# PillEndo-MkI_CAM4.net
KiCad netlist of a schematic drawn in EAGLE
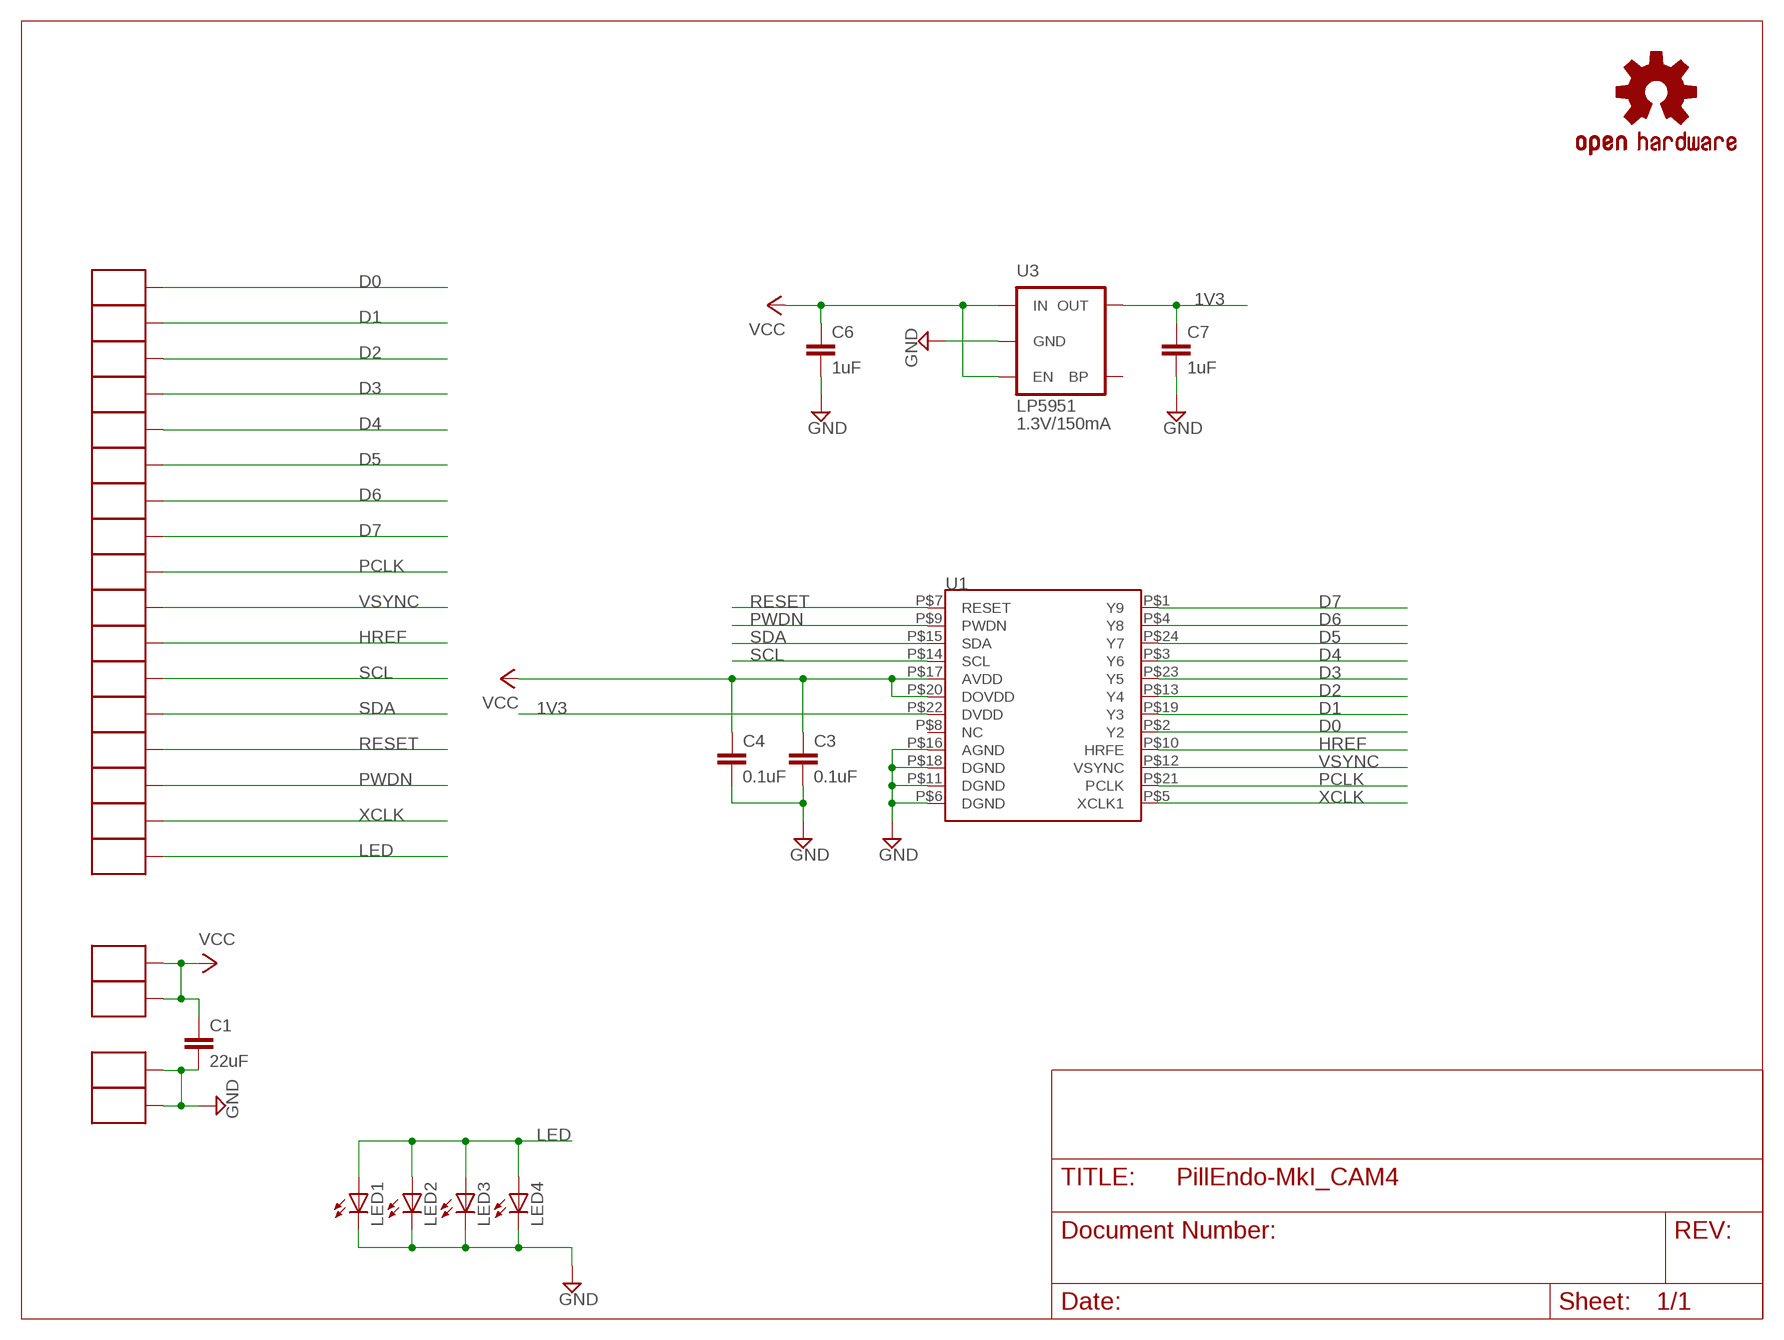
[diagram p0: schematic, sheet 1]

(export (version "E")
  (design (tool "Eeschema 10.0.6"))
  (components
    (comp (ref "C1")
      (value "22uF")
      (footprint "eagle-import:C0603")
      (libsource (lib "eagle-import") (part "C0603"))
    )
    (comp (ref "C3")
      (value "0.1uF")
      (footprint "eagle-import:C0201")
      (libsource (lib "eagle-import") (part "C-EUC0201"))
    )
    (comp (ref "C4")
      (value "0.1uF")
      (footprint "eagle-import:C0201")
      (libsource (lib "eagle-import") (part "C-EUC0201"))
    )
    (comp (ref "C6")
      (value "1uF")
      (footprint "eagle-import:C0402")
      (libsource (lib "eagle-import") (part "C-EUC0402"))
    )
    (comp (ref "C7")
      (value "1uF")
      (footprint "eagle-import:C0402")
      (libsource (lib "eagle-import") (part "C-EUC0402"))
    )
    (comp (ref "LED1")
      (value "LED")
      (footprint "eagle-import:SMARTLED-TTW")
      (libsource (lib "eagle-import") (part "LED"))
    )
    (comp (ref "LED2")
      (value "LED")
      (footprint "eagle-import:SMARTLED-TTW")
      (libsource (lib "eagle-import") (part "LED"))
    )
    (comp (ref "LED3")
      (value "LED")
      (footprint "eagle-import:SMARTLED-TTW")
      (libsource (lib "eagle-import") (part "LED"))
    )
    (comp (ref "LED4")
      (value "LED")
      (footprint "eagle-import:SMARTLED-TTW")
      (libsource (lib "eagle-import") (part "LED"))
    )
    (comp (ref "LOGO1")
      (value "OSHW-LOGOS")
      (footprint "eagle-import:OSHW-LOGO-S")
      (libsource (lib "eagle-import") (part "OSHW-LOGOS"))
    )
    (comp (ref "TP1")
      (value "TP_0.8X0.8")
      (footprint "eagle-import:TP_0.8X0.8")
      (libsource (lib "eagle-import") (part "TP_0.8X0.8"))
    )
    (comp (ref "TP2")
      (value "TP_0.8X0.8")
      (footprint "eagle-import:TP_0.8X0.8")
      (libsource (lib "eagle-import") (part "TP_0.8X0.8"))
    )
    (comp (ref "TP3")
      (value "TP_0.8X0.8")
      (footprint "eagle-import:TP_0.8X0.8")
      (libsource (lib "eagle-import") (part "TP_0.8X0.8"))
    )
    (comp (ref "TP4")
      (value "TP_0.8X0.8")
      (footprint "eagle-import:TP_0.8X0.8")
      (libsource (lib "eagle-import") (part "TP_0.8X0.8"))
    )
    (comp (ref "TP5")
      (value "TP_0.8X0.8")
      (footprint "eagle-import:TP_0.8X0.8")
      (libsource (lib "eagle-import") (part "TP_0.8X0.8"))
    )
    (comp (ref "TP6")
      (value "TP_0.8X0.8")
      (footprint "eagle-import:TP_0.8X0.8")
      (libsource (lib "eagle-import") (part "TP_0.8X0.8"))
    )
    (comp (ref "TP7")
      (value "TP_0.8X0.8")
      (footprint "eagle-import:TP_0.8X0.8")
      (libsource (lib "eagle-import") (part "TP_0.8X0.8"))
    )
    (comp (ref "TP8")
      (value "TP_0.8X0.8")
      (footprint "eagle-import:TP_0.8X0.8")
      (libsource (lib "eagle-import") (part "TP_0.8X0.8"))
    )
    (comp (ref "TP9")
      (value "TP_0.8X0.8")
      (footprint "eagle-import:TP_0.8X0.8")
      (libsource (lib "eagle-import") (part "TP_0.8X0.8"))
    )
    (comp (ref "TP10")
      (value "TP_0.8X0.8")
      (footprint "eagle-import:TP_0.8X0.8")
      (libsource (lib "eagle-import") (part "TP_0.8X0.8"))
    )
    (comp (ref "TP11")
      (value "TP_0.8X0.8")
      (footprint "eagle-import:TP_0.8X0.8")
      (libsource (lib "eagle-import") (part "TP_0.8X0.8"))
    )
    (comp (ref "TP12")
      (value "TP_0.8X0.8")
      (footprint "eagle-import:TP_0.8X0.8")
      (libsource (lib "eagle-import") (part "TP_0.8X0.8"))
    )
    (comp (ref "TP13")
      (value "TP_0.8X0.8")
      (footprint "eagle-import:TP_0.8X0.8")
      (libsource (lib "eagle-import") (part "TP_0.8X0.8"))
    )
    (comp (ref "TP14")
      (value "TP_0.8X0.8")
      (footprint "eagle-import:TP_0.8X0.8")
      (libsource (lib "eagle-import") (part "TP_0.8X0.8"))
    )
    (comp (ref "TP15")
      (value "TP_0.8X0.8")
      (footprint "eagle-import:TP_0.8X0.8")
      (libsource (lib "eagle-import") (part "TP_0.8X0.8"))
    )
    (comp (ref "TP16")
      (value "TP_0.8X0.8")
      (footprint "eagle-import:TP_0.8X0.8")
      (libsource (lib "eagle-import") (part "TP_0.8X0.8"))
    )
    (comp (ref "TP17")
      (value "TP_0.8X0.8")
      (footprint "eagle-import:TP_0.8X0.8")
      (libsource (lib "eagle-import") (part "TP_0.8X0.8"))
    )
    (comp (ref "TP18")
      (value "TP_1.0X1.2")
      (footprint "eagle-import:TP_1.0X1.2")
      (libsource (lib "eagle-import") (part "TP_1.0X1.2"))
    )
    (comp (ref "TP19")
      (value "TP_1.0X1.2")
      (footprint "eagle-import:TP_1.0X1.2")
      (libsource (lib "eagle-import") (part "TP_1.0X1.2"))
    )
    (comp (ref "TP20")
      (value "TP_1.0X1.2")
      (footprint "eagle-import:TP_1.0X1.2")
      (libsource (lib "eagle-import") (part "TP_1.0X1.2"))
    )
    (comp (ref "TP21")
      (value "TP_1.0X1.2")
      (footprint "eagle-import:TP_1.0X1.2")
      (libsource (lib "eagle-import") (part "TP_1.0X1.2"))
    )
    (comp (ref "U1")
      (value "UC2640B")
      (footprint "eagle-import:UC2640B")
      (libsource (lib "eagle-import") (part "UC2640B"))
    )
    (comp (ref "U3")
      (value "1.8V/100mA")
      (footprint "eagle-import:SC70")
      (libsource (lib "eagle-import") (part "V_REG_SP62141.8V"))
    )
  )
  (nets
    (net (code "1") (name "/1V3") (class "Default")
      (node (ref "C7") (pin "1") (pinfunction "1_1") (pintype "passive"))
      (node (ref "U1") (pin "P$22") (pinfunction "DVDD_P$22") (pintype "power_in"))
      (node (ref "U3") (pin "5") (pinfunction "OUT_5") (pintype "passive"))
    )
    (net (code "2") (name "/D0") (class "Default")
      (node (ref "TP11") (pin "P$1") (pinfunction "P$1_P$1") (pintype "passive"))
      (node (ref "U1") (pin "P$2") (pinfunction "Y2_P$2") (pintype "output"))
    )
    (net (code "3") (name "/D1") (class "Default")
      (node (ref "TP1") (pin "P$1") (pinfunction "P$1_P$1") (pintype "passive"))
      (node (ref "U1") (pin "P$19") (pinfunction "Y3_P$19") (pintype "output"))
    )
    (net (code "4") (name "/D2") (class "Default")
      (node (ref "TP9") (pin "P$1") (pinfunction "P$1_P$1") (pintype "passive"))
      (node (ref "U1") (pin "P$13") (pinfunction "Y4_P$13") (pintype "output"))
    )
    (net (code "5") (name "/D3") (class "Default")
      (node (ref "TP3") (pin "P$1") (pinfunction "P$1_P$1") (pintype "passive"))
      (node (ref "U1") (pin "P$23") (pinfunction "Y5_P$23") (pintype "output"))
    )
    (net (code "6") (name "/D4") (class "Default")
      (node (ref "TP12") (pin "P$1") (pinfunction "P$1_P$1") (pintype "passive"))
      (node (ref "U1") (pin "P$3") (pinfunction "Y6_P$3") (pintype "output"))
    )
    (net (code "7") (name "/D5") (class "Default")
      (node (ref "TP4") (pin "P$1") (pinfunction "P$1_P$1") (pintype "passive"))
      (node (ref "U1") (pin "P$24") (pinfunction "Y7_P$24") (pintype "output"))
    )
    (net (code "8") (name "/D6") (class "Default")
      (node (ref "TP13") (pin "P$1") (pinfunction "P$1_P$1") (pintype "passive"))
      (node (ref "U1") (pin "P$4") (pinfunction "Y8_P$4") (pintype "output"))
    )
    (net (code "9") (name "/D7") (class "Default")
      (node (ref "TP10") (pin "P$1") (pinfunction "P$1_P$1") (pintype "passive"))
      (node (ref "U1") (pin "P$1") (pinfunction "Y9_P$1") (pintype "output"))
    )
    (net (code "10") (name "/HREF") (class "Default")
      (node (ref "TP5") (pin "P$1") (pinfunction "P$1_P$1") (pintype "passive"))
      (node (ref "U1") (pin "P$10") (pinfunction "HRFE_P$10") (pintype "output"))
    )
    (net (code "11") (name "/LED") (class "Default")
      (node (ref "LED1") (pin "A@1") (pinfunction "A_A@1") (pintype "passive"))
      (node (ref "LED2") (pin "A@1") (pinfunction "A_A@1") (pintype "passive"))
      (node (ref "LED3") (pin "A@1") (pinfunction "A_A@1") (pintype "passive"))
      (node (ref "LED4") (pin "A@1") (pinfunction "A_A@1") (pintype "passive"))
      (node (ref "TP14") (pin "P$1") (pinfunction "P$1_P$1") (pintype "passive"))
    )
    (net (code "12") (name "/PCLK") (class "Default")
      (node (ref "TP2") (pin "P$1") (pinfunction "P$1_P$1") (pintype "passive"))
      (node (ref "U1") (pin "P$21") (pinfunction "PCLK_P$21") (pintype "output"))
    )
    (net (code "13") (name "/PWDN") (class "Default")
      (node (ref "TP15") (pin "P$1") (pinfunction "P$1_P$1") (pintype "passive"))
      (node (ref "U1") (pin "P$9") (pinfunction "PWDN_P$9") (pintype "input"))
    )
    (net (code "14") (name "/RESET") (class "Default")
      (node (ref "TP17") (pin "P$1") (pinfunction "P$1_P$1") (pintype "passive"))
      (node (ref "U1") (pin "P$7") (pinfunction "RESET_P$7") (pintype "input"))
    )
    (net (code "15") (name "/SCL") (class "Default")
      (node (ref "TP8") (pin "P$1") (pinfunction "P$1_P$1") (pintype "passive"))
      (node (ref "U1") (pin "P$14") (pinfunction "SCL_P$14") (pintype "bidirectional"))
    )
    (net (code "16") (name "/SDA") (class "Default")
      (node (ref "TP7") (pin "P$1") (pinfunction "P$1_P$1") (pintype "passive"))
      (node (ref "U1") (pin "P$15") (pinfunction "SDA_P$15") (pintype "bidirectional"))
    )
    (net (code "17") (name "/VSYNC") (class "Default")
      (node (ref "TP6") (pin "P$1") (pinfunction "P$1_P$1") (pintype "passive"))
      (node (ref "U1") (pin "P$12") (pinfunction "VSYNC_P$12") (pintype "output"))
    )
    (net (code "18") (name "/XCLK") (class "Default")
      (node (ref "TP16") (pin "P$1") (pinfunction "P$1_P$1") (pintype "passive"))
      (node (ref "U1") (pin "P$5") (pinfunction "XCLK1_P$5") (pintype "input"))
    )
    (net (code "19") (name "GND") (class "Default")
      (node (ref "C1") (pin "2") (pinfunction "2_2") (pintype "passive"))
      (node (ref "C3") (pin "2") (pinfunction "2_2") (pintype "passive"))
      (node (ref "C4") (pin "2") (pinfunction "2_2") (pintype "passive"))
      (node (ref "C6") (pin "2") (pinfunction "2_2") (pintype "passive"))
      (node (ref "C7") (pin "2") (pinfunction "2_2") (pintype "passive"))
      (node (ref "LED1") (pin "C@1") (pinfunction "C_C@1") (pintype "passive"))
      (node (ref "LED2") (pin "C@1") (pinfunction "C_C@1") (pintype "passive"))
      (node (ref "LED3") (pin "C@1") (pinfunction "C_C@1") (pintype "passive"))
      (node (ref "LED4") (pin "C@1") (pinfunction "C_C@1") (pintype "passive"))
      (node (ref "TP18") (pin "P$1") (pinfunction "P$1_P$1") (pintype "passive"))
      (node (ref "TP19") (pin "P$1") (pinfunction "P$1_P$1") (pintype "passive"))
      (node (ref "U1") (pin "P$11") (pinfunction "DGND_P$11") (pintype "power_in"))
      (node (ref "U1") (pin "P$16") (pinfunction "AGND_P$16") (pintype "power_in"))
      (node (ref "U1") (pin "P$18") (pinfunction "DGND_P$18") (pintype "power_in"))
      (node (ref "U1") (pin "P$6") (pinfunction "DGND_P$6") (pintype "power_in"))
      (node (ref "U3") (pin "2") (pinfunction "GND_2") (pintype "input"))
    )
    (net (code "20") (name "VCC") (class "Default")
      (node (ref "C1") (pin "1") (pinfunction "1_1") (pintype "passive"))
      (node (ref "C3") (pin "1") (pinfunction "1_1") (pintype "passive"))
      (node (ref "C4") (pin "1") (pinfunction "1_1") (pintype "passive"))
      (node (ref "C6") (pin "1") (pinfunction "1_1") (pintype "passive"))
      (node (ref "TP20") (pin "P$1") (pinfunction "P$1_P$1") (pintype "passive"))
      (node (ref "TP21") (pin "P$1") (pinfunction "P$1_P$1") (pintype "passive"))
      (node (ref "U1") (pin "P$17") (pinfunction "AVDD_P$17") (pintype "power_in"))
      (node (ref "U1") (pin "P$20") (pinfunction "DOVDD_P$20") (pintype "power_in"))
      (node (ref "U3") (pin "1") (pinfunction "IN_1") (pintype "input"))
      (node (ref "U3") (pin "3") (pinfunction "EN_3") (pintype "input"))
    )
    (net (code "21") (name "unconnected-(U1-NC-PadP$8)") (class "Default")
      (node (ref "U1") (pin "P$8") (pinfunction "NC_P$8") (pintype "no_connect"))
    )
    (net (code "22") (name "unconnected-(U3-BP-Pad4)") (class "Default")
      (node (ref "U3") (pin "4") (pinfunction "BP_4") (pintype "input"))
    )
  )
)
